# schematic.net
KiCad netlist of a schematic drawn in EasyEDA
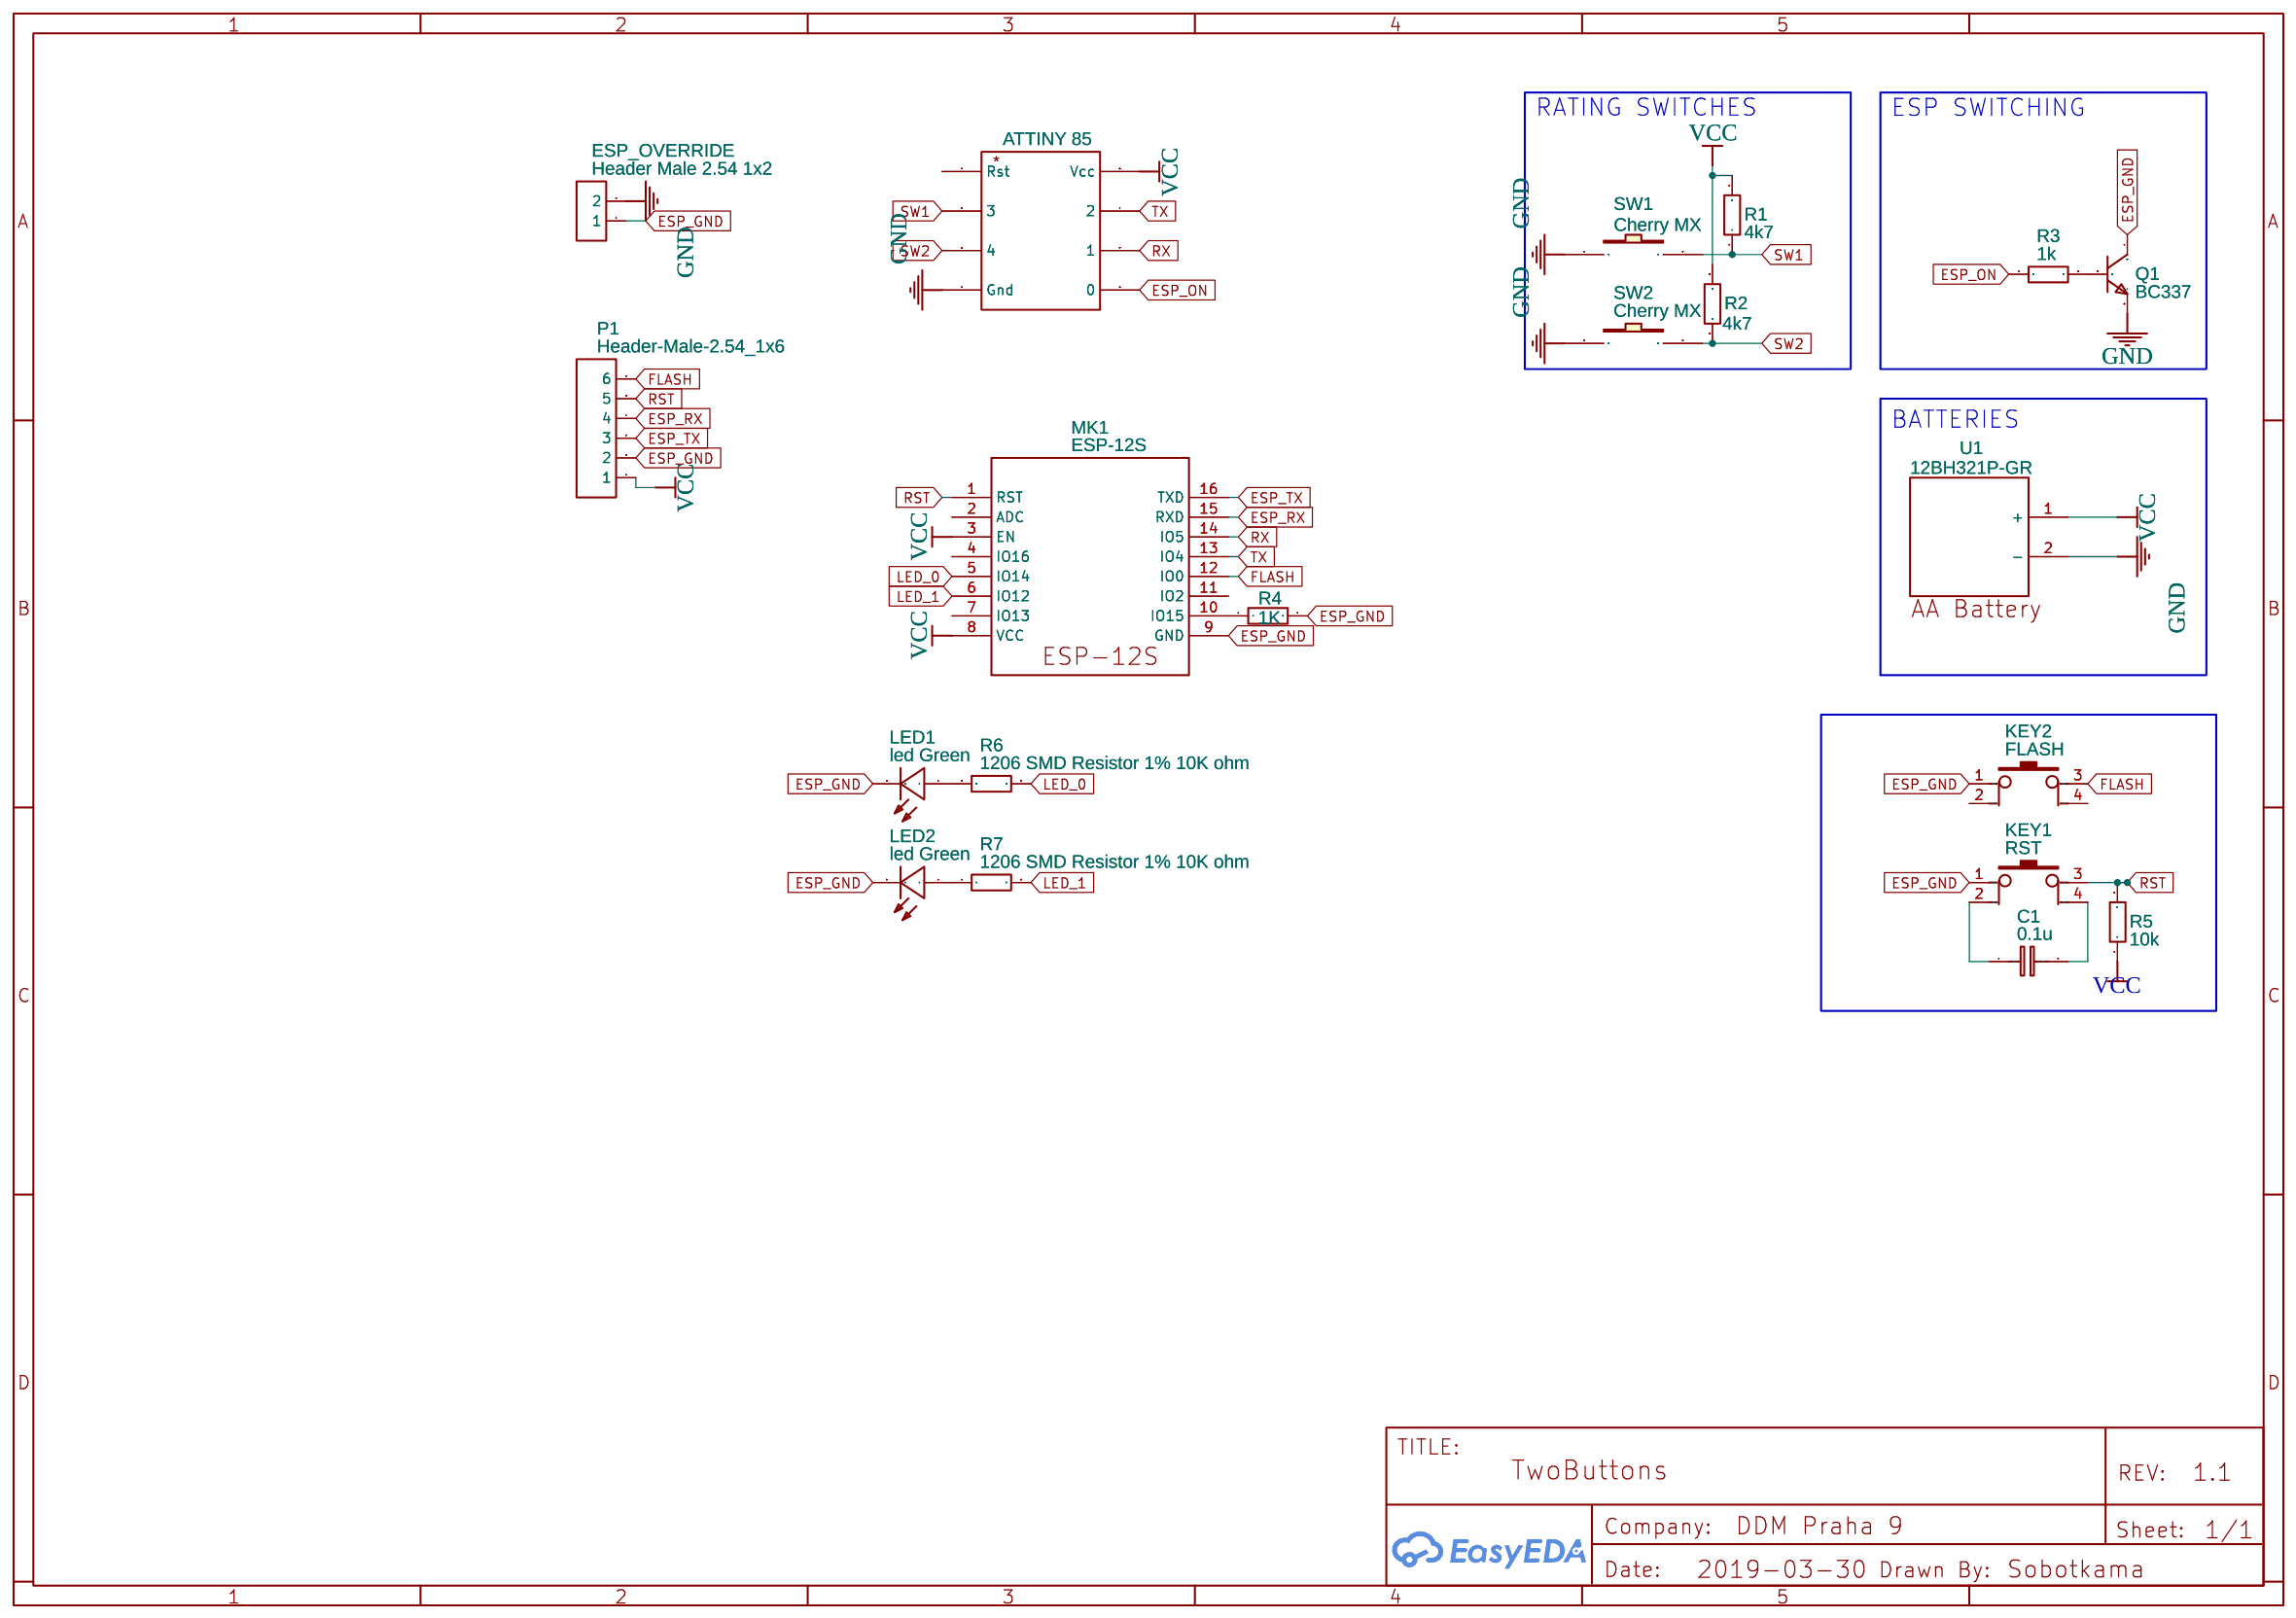
[diagram p0: schematic sheet]

(export (version "E")
  (design (tool "Eeschema 10.0.6"))
  (components
    (comp (ref "ATTINY1")
      (value "ATTINY 85")
      (fields (field (name "BOM_Manufacturer Part") "?"))
      (libsource (lib "") (part "Unknown_540_90"))
    )
    (comp (ref "C1")
      (value "0.1u")
      (fields (field (name "BOM_Manufacturer Part") "?"))
      (libsource (lib "") (part "Cap_RAD-0.1_EU"))
    )
    (comp (ref "ESP_OVERRIDE")
      (value "Header Male 2.54 1x2")
      (fields
        (field (name "BOM_Manufacturer Part") "826629-2")
        (field (name "BOM_Supplier Part") "A105107-ND")
      )
      (libsource (lib "") (part "Unknown_295_100"))
    )
    (comp (ref "KEY1")
      (value "RST")
      (fields
        (field (name "BOM_Manufacturer Part") "button6*6*8")
        (field (name "BOM_Supplier Part") "C59982")
      )
      (libsource (lib "") (part "Unknown_1020_440"))
    )
    (comp (ref "KEY2")
      (value "FLASH")
      (fields
        (field (name "BOM_Manufacturer Part") "button6*6*8")
        (field (name "BOM_Supplier Part") "C59982")
      )
      (libsource (lib "") (part "Unknown_1020_390"))
    )
    (comp (ref "LED1")
      (value "led Green")
      (fields (field (name "BOM_Supplier Part") "C14641"))
      (libsource (lib "") (part "Unknown_455_395"))
    )
    (comp (ref "LED2")
      (value "led Green")
      (fields (field (name "BOM_Supplier Part") "C14641"))
      (libsource (lib "") (part "Unknown_455_445"))
    )
    (comp (ref "MK1")
      (value "ESP-12S")
      (fields (field (name "BOM_Supplier Part") "C82898"))
      (libsource (lib "") (part "Unknown_545_280"))
    )
    (comp (ref "P1")
      (value "Header-Male-2.54_1x6")
      (fields (field (name "BOM_Supplier Part") "C37208"))
      (libsource (lib "") (part "Unknown_300_210"))
    )
    (comp (ref "Q1")
      (value "BC337")
      (fields (field (name "BOM_Supplier Part") "C154963"))
      (libsource (lib "") (part "Unknown_1060_132"))
    )
    (comp (ref "R1")
      (value "4k7")
      (fields
        (field (name "BOM_Manufacturer Part") "MFR0W4F3300A50")
        (field (name "BOM_Supplier Part") "C58608")
      )
      (libsource (lib "") (part "330 Resistor THT (C58608)_2"))
    )
    (comp (ref "R2")
      (value "4k7")
      (fields
        (field (name "BOM_Manufacturer Part") "MFR0W4F3300A50")
        (field (name "BOM_Supplier Part") "C58608")
      )
      (libsource (lib "") (part "330 Resistor THT (C58608)_2"))
    )
    (comp (ref "R3")
      (value "1k")
      (fields
        (field (name "BOM_Manufacturer Part") "MFR0W4F3300A50")
        (field (name "BOM_Supplier Part") "C58608")
      )
      (libsource (lib "") (part "330 Resistor THT (C58608)"))
    )
    (comp (ref "R4")
      (value "1K")
      (fields (field (name "BOM_Supplier Part") "C120055"))
      (libsource (lib "") (part "1K Ohm Resistor THT (C120055)"))
    )
    (comp (ref "R5")
      (value "10k")
      (fields
        (field (name "BOM_Manufacturer Part") "MFR0W4F3300A50")
        (field (name "BOM_Supplier Part") "C58608")
      )
      (libsource (lib "") (part "330 Resistor THT (C58608)_1"))
    )
    (comp (ref "R6") (value "1206 SMD Resistor 1% 10K ohm") (libsource (lib "") (part "Unknown_495_390")))
    (comp (ref "R7") (value "1206 SMD Resistor 1% 10K ohm") (libsource (lib "") (part "Unknown_495_440")))
    (comp (ref "SW1")
      (value "Cherry MX")
      (fields (field (name "BOM_Manufacturer Part") "?"))
      (libsource (lib "") (part "Unknown_825_122"))
    )
    (comp (ref "SW2")
      (value "Cherry MX")
      (fields (field (name "BOM_Manufacturer Part") "?"))
      (libsource (lib "") (part "Unknown_825_167"))
    )
    (comp (ref "U1") (value "12BH321P-GR") (libsource (lib "") (part "Unknown_1020_255")))
  )
  (nets
    (net (code "1") (name "ESP_GND") (class "Default")
      (node (ref "ESP_OVERRIDE") (pin "1") (pinfunction "1_1") (pintype "unspecified"))
      (node (ref "KEY1") (pin "1") (pinfunction "1_1") (pintype "input"))
      (node (ref "KEY2") (pin "1") (pinfunction "1_1") (pintype "input"))
      (node (ref "LED1") (pin "2") (pinfunction "K_2") (pintype "unspecified"))
      (node (ref "LED2") (pin "2") (pinfunction "K_2") (pintype "unspecified"))
      (node (ref "MK1") (pin "9") (pinfunction "GND_9") (pintype "unspecified"))
      (node (ref "P1") (pin "2") (pinfunction "2_2") (pintype "input"))
      (node (ref "Q1") (pin "1") (pinfunction "C_1") (pintype "unspecified"))
      (node (ref "R4") (pin "2") (pinfunction "2_2") (pintype "unspecified"))
    )
    (net (code "2") (name "ESP_ON") (class "Default")
      (node (ref "ATTINY1") (pin "5") (pinfunction "0_5") (pintype "bidirectional"))
      (node (ref "R3") (pin "1") (pinfunction "1_1") (pintype "input"))
    )
    (net (code "3") (name "ESP_RX") (class "Default")
      (node (ref "MK1") (pin "15") (pinfunction "RXD_15") (pintype "unspecified"))
      (node (ref "P1") (pin "4") (pinfunction "4_4") (pintype "input"))
    )
    (net (code "4") (name "ESP_TX") (class "Default")
      (node (ref "MK1") (pin "16") (pinfunction "TXD_16") (pintype "unspecified"))
      (node (ref "P1") (pin "3") (pinfunction "3_3") (pintype "input"))
    )
    (net (code "5") (name "FLASH") (class "Default")
      (node (ref "KEY2") (pin "3") (pinfunction "3_3") (pintype "input"))
      (node (ref "MK1") (pin "12") (pinfunction "IO0_12") (pintype "unspecified"))
      (node (ref "P1") (pin "6") (pinfunction "6_6") (pintype "input"))
    )
    (net (code "6") (name "GND") (class "Default")
      (node (ref "ATTINY1") (pin "4") (pinfunction "Gnd_4") (pintype "passive"))
      (node (ref "ESP_OVERRIDE") (pin "2") (pinfunction "2_2") (pintype "unspecified"))
      (node (ref "Q1") (pin "3") (pinfunction "E_3") (pintype "unspecified"))
      (node (ref "SW1") (pin "1") (pinfunction "1_1") (pintype "input"))
      (node (ref "SW2") (pin "1") (pinfunction "1_1") (pintype "input"))
      (node (ref "U1") (pin "2") (pinfunction "-_2") (pintype "unspecified"))
    )
    (net (code "7") (name "LED_0") (class "Default")
      (node (ref "MK1") (pin "5") (pinfunction "IO14_5") (pintype "unspecified"))
      (node (ref "R6") (pin "2") (pinfunction "2_2") (pintype "input"))
    )
    (net (code "8") (name "LED_1") (class "Default")
      (node (ref "MK1") (pin "6") (pinfunction "IO12_6") (pintype "unspecified"))
      (node (ref "R7") (pin "2") (pinfunction "2_2") (pintype "input"))
    )
    (net (code "9") (name "Net-(C1-Pad1)") (class "Default")
      (node (ref "C1") (pin "1") (pinfunction "1_1") (pintype "unspecified"))
      (node (ref "KEY1") (pin "2") (pinfunction "2_2") (pintype "input"))
    )
    (net (code "10") (name "Net-(C1-Pad2)") (class "Default")
      (node (ref "C1") (pin "2") (pinfunction "2_2") (pintype "unspecified"))
      (node (ref "KEY1") (pin "4") (pinfunction "4_4") (pintype "input"))
    )
    (net (code "11") (name "Net-(LED1-A)") (class "Default")
      (node (ref "LED1") (pin "1") (pinfunction "A_1") (pintype "unspecified"))
      (node (ref "R6") (pin "1") (pinfunction "1_1") (pintype "input"))
    )
    (net (code "12") (name "Net-(LED2-A)") (class "Default")
      (node (ref "LED2") (pin "1") (pinfunction "A_1") (pintype "unspecified"))
      (node (ref "R7") (pin "1") (pinfunction "1_1") (pintype "input"))
    )
    (net (code "13") (name "Net-(MK1-IO15)") (class "Default")
      (node (ref "MK1") (pin "10") (pinfunction "IO15_10") (pintype "unspecified"))
      (node (ref "R4") (pin "1") (pinfunction "1_1") (pintype "unspecified"))
    )
    (net (code "14") (name "Net-(Q1-B)") (class "Default")
      (node (ref "Q1") (pin "2") (pinfunction "B_2") (pintype "unspecified"))
      (node (ref "R3") (pin "2") (pinfunction "2_2") (pintype "input"))
    )
    (net (code "15") (name "RST") (class "Default")
      (node (ref "KEY1") (pin "3") (pinfunction "3_3") (pintype "input"))
      (node (ref "MK1") (pin "1") (pinfunction "RST_1") (pintype "unspecified"))
      (node (ref "P1") (pin "5") (pinfunction "5_5") (pintype "input"))
      (node (ref "R5") (pin "2") (pinfunction "2_2") (pintype "input"))
    )
    (net (code "16") (name "RX") (class "Default")
      (node (ref "ATTINY1") (pin "6") (pinfunction "1_6") (pintype "bidirectional"))
      (node (ref "MK1") (pin "14") (pinfunction "IO5_14") (pintype "unspecified"))
    )
    (net (code "17") (name "SW1") (class "Default")
      (node (ref "ATTINY1") (pin "2") (pinfunction "3_2") (pintype "bidirectional"))
      (node (ref "R1") (pin "1") (pinfunction "1_1") (pintype "input"))
      (node (ref "SW1") (pin "2") (pinfunction "2_2") (pintype "input"))
    )
    (net (code "18") (name "SW2") (class "Default")
      (node (ref "ATTINY1") (pin "3") (pinfunction "4_3") (pintype "bidirectional"))
      (node (ref "R2") (pin "1") (pinfunction "1_1") (pintype "input"))
      (node (ref "SW2") (pin "2") (pinfunction "2_2") (pintype "input"))
    )
    (net (code "19") (name "TX") (class "Default")
      (node (ref "ATTINY1") (pin "7") (pinfunction "2_7") (pintype "bidirectional"))
      (node (ref "MK1") (pin "13") (pinfunction "IO4_13") (pintype "unspecified"))
    )
    (net (code "20") (name "VCC") (class "Default")
      (node (ref "ATTINY1") (pin "8") (pinfunction "Vcc_8") (pintype "passive"))
      (node (ref "MK1") (pin "3") (pinfunction "EN_3") (pintype "unspecified"))
      (node (ref "MK1") (pin "8") (pinfunction "VCC_8") (pintype "unspecified"))
      (node (ref "P1") (pin "1") (pinfunction "1_1") (pintype "input"))
      (node (ref "R1") (pin "2") (pinfunction "2_2") (pintype "input"))
      (node (ref "R2") (pin "2") (pinfunction "2_2") (pintype "input"))
      (node (ref "R5") (pin "1") (pinfunction "1_1") (pintype "input"))
      (node (ref "U1") (pin "1") (pinfunction "+_1") (pintype "unspecified"))
    )
    (net (code "21") (name "unconnected-(ATTINY1-Rst-Pad1)") (class "Default")
      (node (ref "ATTINY1") (pin "1") (pinfunction "Rst_1") (pintype "unspecified"))
    )
    (net (code "22") (name "unconnected-(KEY2-Pad2)") (class "Default")
      (node (ref "KEY2") (pin "2") (pinfunction "2_2") (pintype "input"))
    )
    (net (code "23") (name "unconnected-(KEY2-Pad4)") (class "Default")
      (node (ref "KEY2") (pin "4") (pinfunction "4_4") (pintype "input"))
    )
    (net (code "24") (name "unconnected-(MK1-ADC-Pad2)") (class "Default")
      (node (ref "MK1") (pin "2") (pinfunction "ADC_2") (pintype "unspecified"))
    )
    (net (code "25") (name "unconnected-(MK1-IO2-Pad11)") (class "Default")
      (node (ref "MK1") (pin "11") (pinfunction "IO2_11") (pintype "unspecified"))
    )
    (net (code "26") (name "unconnected-(MK1-IO13-Pad7)") (class "Default")
      (node (ref "MK1") (pin "7") (pinfunction "IO13_7") (pintype "unspecified"))
    )
    (net (code "27") (name "unconnected-(MK1-IO16-Pad4)") (class "Default")
      (node (ref "MK1") (pin "4") (pinfunction "IO16_4") (pintype "unspecified"))
    )
  )
)
